# tram_stop.net
KiCad netlist of a schematic drawn in EAGLE
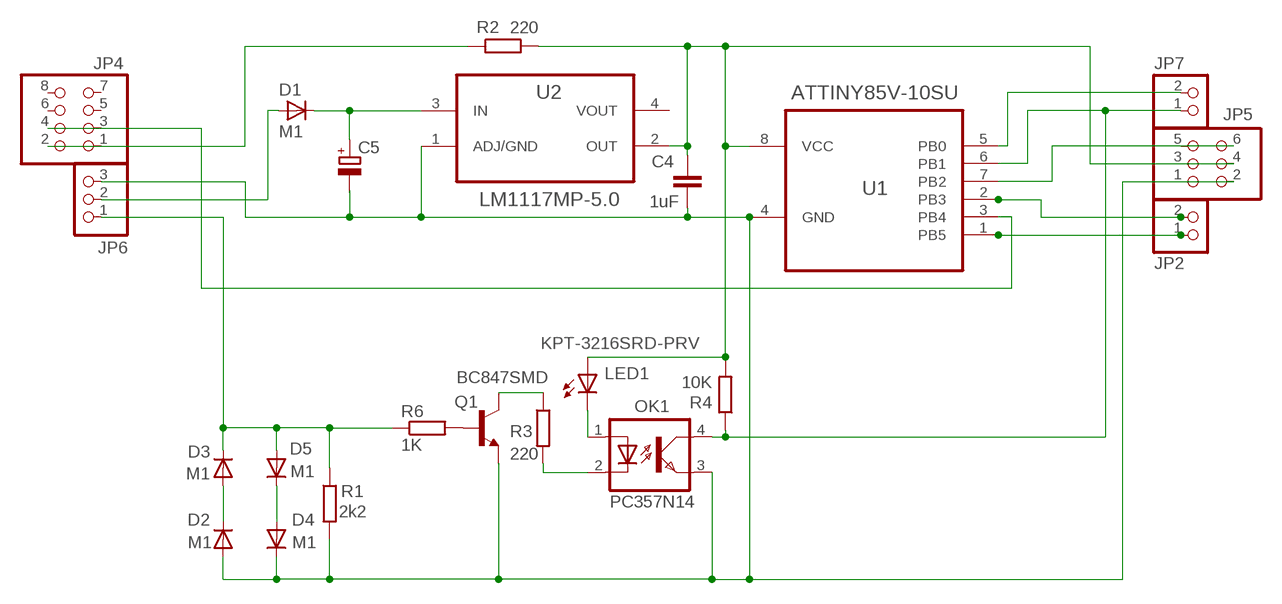
[diagram p0: schematic, sheet 1]

(export (version "E")
  (design (tool "Eeschema 10.0.6"))
  (components
    (comp (ref "C4")
      (value "1uF")
      (footprint "eagle-import:C0402")
      (libsource (lib "eagle-import") (part "C-EUC0402"))
    )
    (comp (ref "C5")
      (value "CPOL-EUSMCD")
      (footprint "eagle-import:SMC_D")
      (libsource (lib "eagle-import") (part "CPOL-EUSMCD"))
    )
    (comp (ref "D1")
      (value "M1")
      (footprint "eagle-import:SMB")
      (libsource (lib "eagle-import") (part "ES2D"))
    )
    (comp (ref "D2")
      (value "M1")
      (footprint "eagle-import:SMB")
      (libsource (lib "eagle-import") (part "ES2D"))
    )
    (comp (ref "D3")
      (value "M1")
      (footprint "eagle-import:SMB")
      (libsource (lib "eagle-import") (part "ES2D"))
    )
    (comp (ref "D4")
      (value "M1")
      (footprint "eagle-import:SMB")
      (libsource (lib "eagle-import") (part "ES2D"))
    )
    (comp (ref "D5")
      (value "M1")
      (footprint "eagle-import:SMB")
      (libsource (lib "eagle-import") (part "ES2D"))
    )
    (comp (ref "JP2")
      (value "PINHD-1X2/90")
      (footprint "eagle-import:1X02_90")
      (libsource (lib "eagle-import") (part "PINHD-1X2/90"))
    )
    (comp (ref "JP4")
      (value "PINHD-2X4/90")
      (footprint "eagle-import:2X04_90")
      (libsource (lib "eagle-import") (part "PINHD-2X4/90"))
    )
    (comp (ref "JP5")
      (value "PINHD-2X3/90")
      (footprint "eagle-import:2X03_90")
      (libsource (lib "eagle-import") (part "PINHD-2X3/90"))
    )
    (comp (ref "JP6")
      (value "PINHD-1X3/90")
      (footprint "eagle-import:1X03_90")
      (libsource (lib "eagle-import") (part "PINHD-1X3/90"))
    )
    (comp (ref "JP7")
      (value "PINHD-1X2/90")
      (footprint "eagle-import:1X02_90")
      (libsource (lib "eagle-import") (part "PINHD-1X2/90"))
    )
    (comp (ref "LED1")
      (value "KPT-3216SRD-PRV")
      (footprint "eagle-import:SML1206")
      (libsource (lib "eagle-import") (part "LEDSML1206"))
    )
    (comp (ref "OK1")
      (value "PC357N14")
      (footprint "eagle-import:SMD4")
      (libsource (lib "eagle-import") (part "LTV816S"))
    )
    (comp (ref "Q1")
      (value "BC847SMD")
      (footprint "eagle-import:SOT23")
      (libsource (lib "eagle-import") (part "BC847SMD"))
    )
    (comp (ref "R1")
      (value "2k2")
      (footprint "eagle-import:R1206")
      (libsource (lib "eagle-import") (part "R-EU_R1206"))
    )
    (comp (ref "R2")
      (value "220")
      (footprint "eagle-import:R1206")
      (libsource (lib "eagle-import") (part "R-EU_R1206"))
    )
    (comp (ref "R3")
      (value "220")
      (footprint "eagle-import:R1206")
      (libsource (lib "eagle-import") (part "R-EU_R1206"))
    )
    (comp (ref "R4")
      (value "10K")
      (footprint "eagle-import:R1206")
      (libsource (lib "eagle-import") (part "R-EU_R1206"))
    )
    (comp (ref "R6")
      (value "1K")
      (footprint "eagle-import:R1206")
      (libsource (lib "eagle-import") (part "R-EU_R1206"))
    )
    (comp (ref "U1")
      (value "ATTINY85V-10SU")
      (footprint "eagle-import:SOIC127P798X216-8N")
      (libsource (lib "eagle-import") (part "ATTINY85V-10SU"))
    )
    (comp (ref "U2")
      (value "LM1117MP-5.0")
      (footprint "eagle-import:SOT230P696X180-4N")
      (libsource (lib "eagle-import") (part "LM1117MP-5.0"))
    )
  )
  (nets
    (net (code "1") (name "Net-(D1-PadA)") (class "Default")
      (node (ref "D1") (pin "A") (pinfunction "A_A") (pintype "passive"))
      (node (ref "JP6") (pin "2") (pinfunction "2_2") (pintype "passive"))
    )
    (net (code "2") (name "Net-(D2-PadC)") (class "Default")
      (node (ref "D2") (pin "C") (pinfunction "C_C") (pintype "passive"))
      (node (ref "D3") (pin "A") (pinfunction "A_A") (pintype "passive"))
    )
    (net (code "3") (name "Net-(D3-PadC)") (class "Default")
      (node (ref "D3") (pin "C") (pinfunction "C_C") (pintype "passive"))
      (node (ref "D5") (pin "A") (pinfunction "A_A") (pintype "passive"))
      (node (ref "JP6") (pin "1") (pinfunction "1_1") (pintype "passive"))
      (node (ref "R1") (pin "1") (pinfunction "1_1") (pintype "passive"))
      (node (ref "R6") (pin "1") (pinfunction "1_1") (pintype "passive"))
    )
    (net (code "4") (name "Net-(D4-PadA)") (class "Default")
      (node (ref "D4") (pin "A") (pinfunction "A_A") (pintype "passive"))
      (node (ref "D5") (pin "C") (pinfunction "C_C") (pintype "passive"))
    )
    (net (code "5") (name "Net-(JP4-Pad1)") (class "Default")
      (node (ref "JP4") (pin "1") (pinfunction "1_1") (pintype "passive"))
      (node (ref "JP4") (pin "2") (pinfunction "2_2") (pintype "passive"))
      (node (ref "R2") (pin "1") (pinfunction "1_1") (pintype "passive"))
    )
    (net (code "6") (name "Net-(OK1-A)") (class "Default")
      (node (ref "LED1") (pin "C") (pinfunction "C_C") (pintype "passive"))
      (node (ref "OK1") (pin "1") (pinfunction "A_1") (pintype "passive"))
    )
    (net (code "7") (name "Net-(OK1-C)") (class "Default")
      (node (ref "OK1") (pin "2") (pinfunction "C_2") (pintype "passive"))
      (node (ref "R3") (pin "2") (pinfunction "2_2") (pintype "passive"))
    )
    (net (code "8") (name "Net-(OK1-COL)") (class "Default")
      (node (ref "JP7") (pin "1") (pinfunction "1_1") (pintype "passive"))
      (node (ref "OK1") (pin "4") (pinfunction "COL_4") (pintype "passive"))
      (node (ref "R4") (pin "1") (pinfunction "1_1") (pintype "passive"))
      (node (ref "U1") (pin "6") (pinfunction "PB1_6") (pintype "bidirectional"))
    )
    (net (code "9") (name "Net-(OK1-EMIT)") (class "Default")
      (node (ref "C4") (pin "2") (pinfunction "2_2") (pintype "passive"))
      (node (ref "D2") (pin "A") (pinfunction "A_A") (pintype "passive"))
      (node (ref "D4") (pin "C") (pinfunction "C_C") (pintype "passive"))
      (node (ref "JP5") (pin "1") (pinfunction "1_1") (pintype "passive"))
      (node (ref "JP5") (pin "2") (pinfunction "2_2") (pintype "passive"))
      (node (ref "JP6") (pin "3") (pinfunction "3_3") (pintype "passive"))
      (node (ref "OK1") (pin "3") (pinfunction "EMIT_3") (pintype "passive"))
      (node (ref "Q1") (pin "2") (pinfunction "E_2") (pintype "passive"))
      (node (ref "R1") (pin "2") (pinfunction "2_2") (pintype "passive"))
      (node (ref "U1") (pin "4") (pinfunction "GND_4") (pintype "passive"))
      (node (ref "U2") (pin "1") (pinfunction "ADJ/GND_1") (pintype "passive"))
    )
    (net (code "10") (name "Net-(Q1-B)") (class "Default")
      (node (ref "Q1") (pin "1") (pinfunction "B_1") (pintype "passive"))
      (node (ref "R6") (pin "2") (pinfunction "2_2") (pintype "passive"))
    )
    (net (code "11") (name "Net-(Q1-C)") (class "Default")
      (node (ref "Q1") (pin "3") (pinfunction "C_3") (pintype "passive"))
      (node (ref "R3") (pin "1") (pinfunction "1_1") (pintype "passive"))
    )
    (net (code "12") (name "Net-(U1-PB0)") (class "Default")
      (node (ref "JP7") (pin "2") (pinfunction "2_2") (pintype "passive"))
      (node (ref "U1") (pin "5") (pinfunction "PB0_5") (pintype "bidirectional"))
    )
    (net (code "13") (name "Net-(U1-PB2)") (class "Default")
      (node (ref "JP5") (pin "5") (pinfunction "5_5") (pintype "passive"))
      (node (ref "JP5") (pin "6") (pinfunction "6_6") (pintype "passive"))
      (node (ref "U1") (pin "7") (pinfunction "PB2_7") (pintype "bidirectional"))
    )
    (net (code "14") (name "Net-(U1-PB3)") (class "Default")
      (node (ref "JP2") (pin "2") (pinfunction "2_2") (pintype "passive"))
      (node (ref "U1") (pin "2") (pinfunction "PB3_2") (pintype "bidirectional"))
    )
    (net (code "15") (name "Net-(U1-PB4)") (class "Default")
      (node (ref "JP4") (pin "3") (pinfunction "3_3") (pintype "passive"))
      (node (ref "JP4") (pin "4") (pinfunction "4_4") (pintype "passive"))
      (node (ref "U1") (pin "3") (pinfunction "PB4_3") (pintype "bidirectional"))
    )
    (net (code "16") (name "Net-(U1-PB5)") (class "Default")
      (node (ref "JP2") (pin "1") (pinfunction "1_1") (pintype "passive"))
      (node (ref "U1") (pin "1") (pinfunction "PB5_1") (pintype "bidirectional"))
    )
    (net (code "17") (name "Net-(U1-VCC)") (class "Default")
      (node (ref "C4") (pin "1") (pinfunction "1_1") (pintype "passive"))
      (node (ref "JP5") (pin "3") (pinfunction "3_3") (pintype "passive"))
      (node (ref "JP5") (pin "4") (pinfunction "4_4") (pintype "passive"))
      (node (ref "LED1") (pin "A") (pinfunction "A_A") (pintype "passive"))
      (node (ref "R2") (pin "2") (pinfunction "2_2") (pintype "passive"))
      (node (ref "R4") (pin "2") (pinfunction "2_2") (pintype "passive"))
      (node (ref "U1") (pin "8") (pinfunction "VCC_8") (pintype "power_in"))
      (node (ref "U2") (pin "2") (pinfunction "OUT_2") (pintype "output"))
    )
    (net (code "18") (name "Net-(U2-IN)") (class "Default")
      (node (ref "C5") (pin "+") (pinfunction "+_+") (pintype "passive"))
      (node (ref "D1") (pin "C") (pinfunction "C_C") (pintype "passive"))
      (node (ref "U2") (pin "3") (pinfunction "IN_3") (pintype "input"))
    )
    (net (code "19") (name "unconnected-(C5-Pad-)") (class "Default")
      (node (ref "C5") (pin "-") (pinfunction "-_-") (pintype "passive"))
    )
    (net (code "20") (name "unconnected-(JP4-Pad5)") (class "Default")
      (node (ref "JP4") (pin "5") (pinfunction "5_5") (pintype "passive"))
    )
    (net (code "21") (name "unconnected-(JP4-Pad6)") (class "Default")
      (node (ref "JP4") (pin "6") (pinfunction "6_6") (pintype "passive"))
    )
    (net (code "22") (name "unconnected-(JP4-Pad7)") (class "Default")
      (node (ref "JP4") (pin "7") (pinfunction "7_7") (pintype "passive"))
    )
    (net (code "23") (name "unconnected-(JP4-Pad8)") (class "Default")
      (node (ref "JP4") (pin "8") (pinfunction "8_8") (pintype "passive"))
    )
    (net (code "24") (name "unconnected-(U2-VOUT-Pad4)") (class "Default")
      (node (ref "U2") (pin "4") (pinfunction "VOUT_4") (pintype "output"))
    )
  )
)
